# Audio.net
KiCad netlist of a schematic drawn in Altium Designer
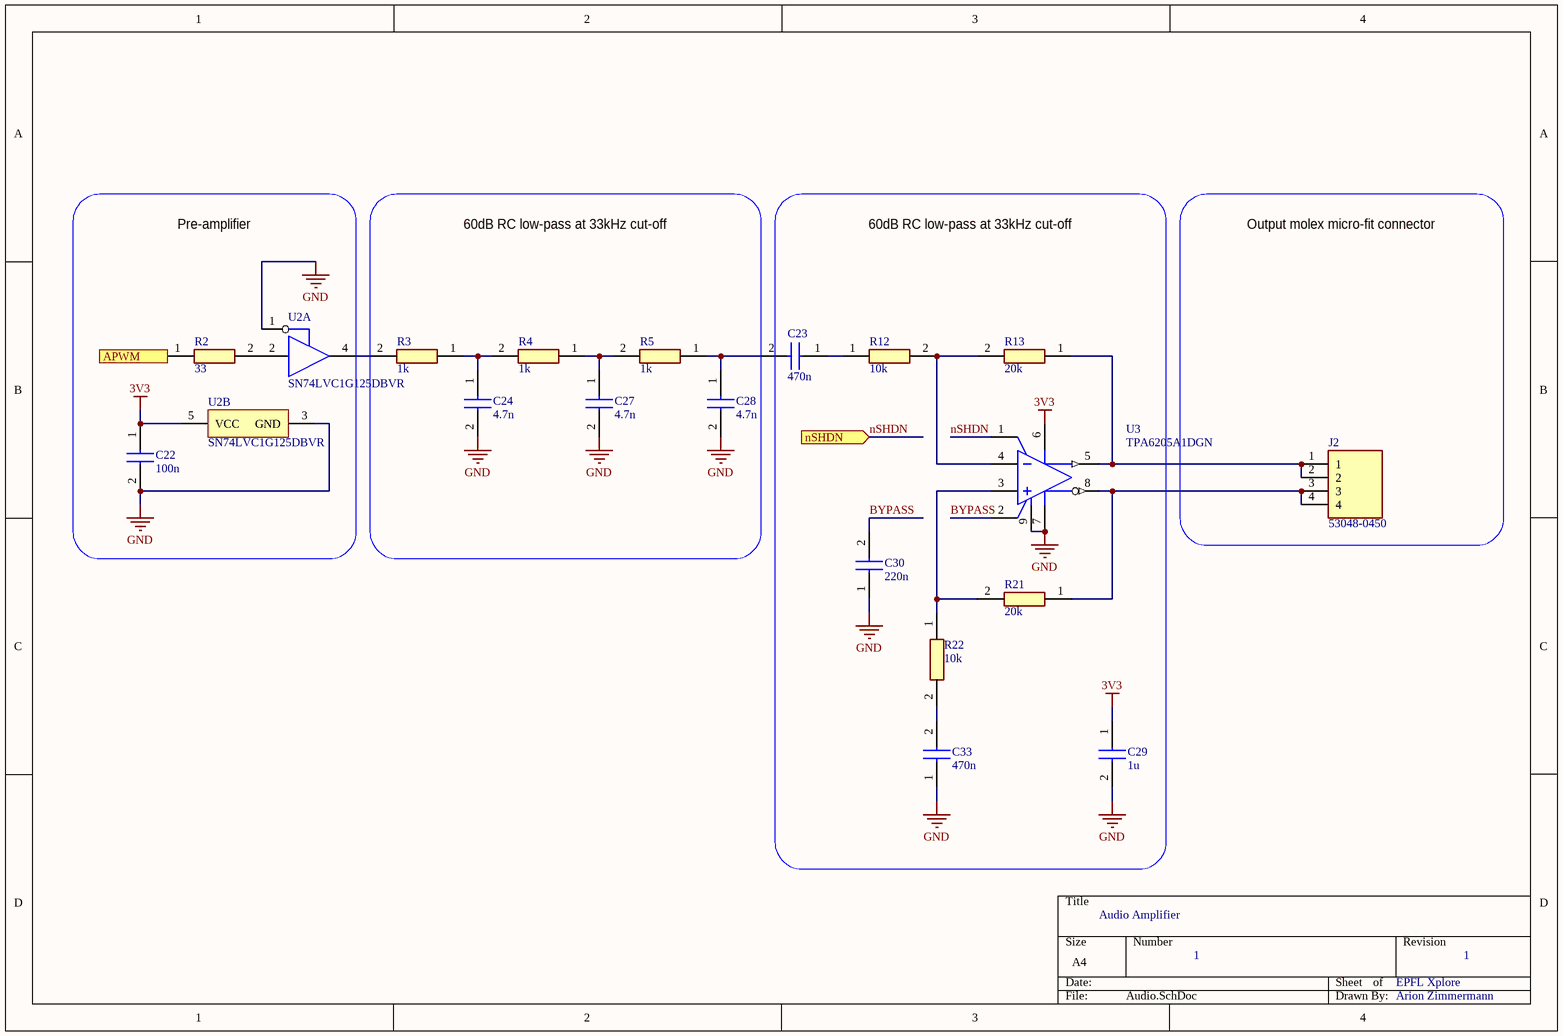
[diagram p0: Audio.SchDoc]

(export (version "E")
  (design (tool "Eeschema 10.0.6"))
  (components
    (comp (ref "C22")
      (value "100n")
      (footprint "SamacSys:CAPC1608X95N")
      (description "Capacitor")
      (fields
        (field (name "MANUFACTURER_PART_NUMBER") "C0603C104K5RACTU")
        (field (name "MOUSER PART NUMBER") "80-C0603C104K5R")
      )
      (libsource (lib "CarrierBoard") (part "C0603C104K5RACTU"))
    )
    (comp (ref "C23")
      (value "470n")
      (footprint "SamacSys:CAPC1608X95N")
      (description "Capacitor")
      (fields
        (field (name "MANUFACTURER_PART_NUMBER") "C0603C104K5RACTU")
        (field (name "MOUSER PART NUMBER") "80-C0603C104K5R")
      )
      (libsource (lib "CarrierBoard") (part "C0603C104K5RACTU"))
    )
    (comp (ref "C24")
      (value "4.7n")
      (footprint "SamacSys:CAPC1608X95N")
      (description "Capacitor")
      (fields
        (field (name "MANUFACTURER_PART_NUMBER") "C0603C104K5RACTU")
        (field (name "MOUSER PART NUMBER") "80-C0603C104K5R")
      )
      (libsource (lib "CarrierBoard") (part "C0603C104K5RACTU"))
    )
    (comp (ref "C27")
      (value "4.7n")
      (footprint "SamacSys:CAPC1608X95N")
      (description "Capacitor")
      (fields
        (field (name "MANUFACTURER_PART_NUMBER") "C0603C104K5RACTU")
        (field (name "MOUSER PART NUMBER") "80-C0603C104K5R")
      )
      (libsource (lib "CarrierBoard") (part "C0603C104K5RACTU"))
    )
    (comp (ref "C28")
      (value "4.7n")
      (footprint "SamacSys:CAPC1608X95N")
      (description "Capacitor")
      (fields
        (field (name "MANUFACTURER_PART_NUMBER") "C0603C104K5RACTU")
        (field (name "MOUSER PART NUMBER") "80-C0603C104K5R")
      )
      (libsource (lib "CarrierBoard") (part "C0603C104K5RACTU"))
    )
    (comp (ref "C29")
      (value "1u")
      (footprint "SamacSys:CAPC1608X95N")
      (description "Capacitor")
      (fields
        (field (name "MANUFACTURER_PART_NUMBER") "C0603C104K5RACTU")
        (field (name "MOUSER PART NUMBER") "80-C0603C104K5R")
      )
      (libsource (lib "CarrierBoard") (part "C0603C104K5RACTU"))
    )
    (comp (ref "C30")
      (value "220n")
      (footprint "SamacSys:CAPC1608X95N")
      (description "Capacitor")
      (fields
        (field (name "MANUFACTURER_PART_NUMBER") "C0603C104K5RACTU")
        (field (name "MOUSER PART NUMBER") "80-C0603C104K5R")
      )
      (libsource (lib "CarrierBoard") (part "C0603C104K5RACTU"))
    )
    (comp (ref "C33")
      (value "470n")
      (footprint "SamacSys:CAPC1608X95N")
      (description "Capacitor")
      (fields
        (field (name "MANUFACTURER_PART_NUMBER") "C0603C104K5RACTU")
        (field (name "MOUSER PART NUMBER") "80-C0603C104K5R")
      )
      (libsource (lib "CarrierBoard") (part "C0603C104K5RACTU"))
    )
    (comp (ref "J2")
      (value "53048-0450")
      (footprint "SHDRRA4W35P0X125_1X4_675X550X350P")
      (description "Connector")
      (fields (field (name "MOUSER PART NUMBER") "538-53048-0450"))
      (libsource (lib "*") (part "53048-0450"))
    )
    (comp (ref "R2")
      (value "33")
      (footprint "SamacSys:RESC1608X50N")
      (description "Resistor")
      (fields
        (field (name "MANUFACTURER_PART_NUMBER") "CRCW0603787RFKEA")
        (field (name "Comment") "CRCW060333R0JNEAC")
      )
      (libsource (lib "CarrierBoard") (part "CRCW0603931RFKEA"))
    )
    (comp (ref "R3")
      (value "1k")
      (footprint "SamacSys:RESC1608X50N")
      (description "Resistor")
      (fields
        (field (name "MANUFACTURER_PART_NUMBER") "CRCW0603787RFKEA")
        (field (name "Comment") "CRCW06031K00FKECC")
      )
      (libsource (lib "") (part "CRCW0603931RFKEA_1"))
    )
    (comp (ref "R4")
      (value "1k")
      (footprint "SamacSys:RESC1608X50N")
      (description "Resistor")
      (fields
        (field (name "MANUFACTURER_PART_NUMBER") "CRCW0603787RFKEA")
        (field (name "Comment") "CRCW06031K00FKECC")
      )
      (libsource (lib "") (part "CRCW0603931RFKEA_1"))
    )
    (comp (ref "R5")
      (value "1k")
      (footprint "SamacSys:RESC1608X50N")
      (description "Resistor")
      (fields
        (field (name "MANUFACTURER_PART_NUMBER") "CRCW0603787RFKEA")
        (field (name "Comment") "CRCW06031K00FKECC")
      )
      (libsource (lib "") (part "CRCW0603931RFKEA_1"))
    )
    (comp (ref "R12")
      (value "10k")
      (footprint "SamacSys:RESC1608X50N")
      (description "Resistor")
      (fields
        (field (name "MANUFACTURER_PART_NUMBER") "CRCW0603787RFKEA")
        (field (name "Comment") "CRCW060310K2FKEA")
      )
      (libsource (lib "CarrierBoard") (part "CRCW0603931RFKEA"))
    )
    (comp (ref "R13")
      (value "20k")
      (footprint "SamacSys:RESC1608X50N")
      (description "Resistor")
      (fields
        (field (name "MANUFACTURER_PART_NUMBER") "CRCW0603787RFKEA")
        (field (name "Comment") "CRCW060320K0FKEAC")
      )
      (libsource (lib "") (part "CRCW0603931RFKEA_1"))
    )
    (comp (ref "R21")
      (value "20k")
      (footprint "SamacSys:RESC1608X50N")
      (description "Resistor")
      (fields
        (field (name "MANUFACTURER_PART_NUMBER") "CRCW0603787RFKEA")
        (field (name "Comment") "CRCW060320K0FKEAC")
      )
      (libsource (lib "") (part "CRCW0603931RFKEA_1"))
    )
    (comp (ref "R22")
      (value "10k")
      (footprint "SamacSys:RESC1608X50N")
      (description "Resistor")
      (fields
        (field (name "MANUFACTURER_PART_NUMBER") "CRCW0603787RFKEA")
        (field (name "Comment") "CRCW060310K2FKEA")
      )
      (libsource (lib "") (part "CRCW0603931RFKEA_2"))
    )
    (comp (ref "U2")
      (value "SN74LVC1G125DBVR")
      (footprint "DBV0005A_M")
      (description "Single Bus Buffer Gate With 3-State Outputs, DBV0005A, LARGE T&R")
      (fields
        (field (name "GENERIC PART NUMBER") "SN74LVC1G125")
        (field (name "MANUFACTURER") "Texas Instruments")
      )
      (libsource (lib "") (part "TI-SN74AXXXX1X125-5_1"))
    )
    (comp (ref "U3")
      (value "TPA6205A1DGN")
      (footprint "DGN0008D_N")
      (fields (field (name "MANUFACTURER") "Texas Instruments"))
      (libsource (lib "Altium Content Vault") (part "TI-TPA62XXA1DXX8-TP"))
    )
  )
  (nets
    (net (code "1") (name "/APWM") (class "Default")
      (node (ref "R2") (pin "1") (pinfunction "1_1") (pintype "passive"))
    )
    (net (code "2") (name "/BYPASS") (class "Default")
      (node (ref "C30") (pin "2") (pinfunction "2_2") (pintype "passive"))
      (node (ref "U3") (pin "2") (pinfunction "BYPASS_2") (pintype "passive"))
    )
    (net (code "3") (name "/nSHDN") (class "Default")
      (node (ref "U3") (pin "1") (pinfunction "~{SHUTDOWN}_1") (pintype "passive"))
    )
    (net (code "4") (name "3V3") (class "Default")
      (node (ref "C22") (pin "1") (pinfunction "1_1") (pintype "passive"))
      (node (ref "C29") (pin "1") (pinfunction "1_1") (pintype "passive"))
      (node (ref "U2") (pin "5") (pinfunction "VCC_5") (pintype "power_in"))
      (node (ref "U3") (pin "6") (pinfunction "VDD_6") (pintype "power_in"))
    )
    (net (code "5") (name "GND") (class "Default")
      (node (ref "C22") (pin "2") (pinfunction "2_2") (pintype "passive"))
      (node (ref "C24") (pin "2") (pinfunction "2_2") (pintype "passive"))
      (node (ref "C27") (pin "2") (pinfunction "2_2") (pintype "passive"))
      (node (ref "C28") (pin "2") (pinfunction "2_2") (pintype "passive"))
      (node (ref "C29") (pin "2") (pinfunction "2_2") (pintype "passive"))
      (node (ref "C30") (pin "1") (pinfunction "1_1") (pintype "passive"))
      (node (ref "C33") (pin "1") (pinfunction "1_1") (pintype "passive"))
      (node (ref "U2") (pin "1") (pinfunction "~{OE}_1") (pintype "passive"))
      (node (ref "U2") (pin "3") (pinfunction "GND_3") (pintype "power_in"))
      (node (ref "U3") (pin "7") (pinfunction "GND_7") (pintype "power_in"))
      (node (ref "U3") (pin "9") (pinfunction "EP_9") (pintype "power_in"))
    )
    (net (code "6") (name "Net-(C23-Pad1)") (class "Default")
      (node (ref "C23") (pin "1") (pinfunction "1_1") (pintype "passive"))
      (node (ref "R12") (pin "1") (pinfunction "1_1") (pintype "passive"))
    )
    (net (code "7") (name "Net-(C23-Pad2)") (class "Default")
      (node (ref "C23") (pin "2") (pinfunction "2_2") (pintype "passive"))
      (node (ref "C28") (pin "1") (pinfunction "1_1") (pintype "passive"))
      (node (ref "R5") (pin "1") (pinfunction "1_1") (pintype "passive"))
    )
    (net (code "8") (name "Net-(C24-Pad1)") (class "Default")
      (node (ref "C24") (pin "1") (pinfunction "1_1") (pintype "passive"))
      (node (ref "R3") (pin "1") (pinfunction "1_1") (pintype "passive"))
      (node (ref "R4") (pin "2") (pinfunction "2_2") (pintype "passive"))
    )
    (net (code "9") (name "Net-(C27-Pad1)") (class "Default")
      (node (ref "C27") (pin "1") (pinfunction "1_1") (pintype "passive"))
      (node (ref "R4") (pin "1") (pinfunction "1_1") (pintype "passive"))
      (node (ref "R5") (pin "2") (pinfunction "2_2") (pintype "passive"))
    )
    (net (code "10") (name "Net-(C33-Pad2)") (class "Default")
      (node (ref "C33") (pin "2") (pinfunction "2_2") (pintype "passive"))
      (node (ref "R22") (pin "2") (pinfunction "2_2") (pintype "passive"))
    )
    (net (code "11") (name "Net-(U2A-A)") (class "Default")
      (node (ref "R2") (pin "2") (pinfunction "2_2") (pintype "passive"))
      (node (ref "U2") (pin "2") (pinfunction "A_2") (pintype "passive"))
    )
    (net (code "12") (name "Net-(U2A-Y)") (class "Default")
      (node (ref "R3") (pin "2") (pinfunction "2_2") (pintype "passive"))
      (node (ref "U2") (pin "4") (pinfunction "Y_4") (pintype "tri_state"))
    )
    (net (code "13") (name "Net-(U3-IN+)") (class "Default")
      (node (ref "R21") (pin "2") (pinfunction "2_2") (pintype "passive"))
      (node (ref "R22") (pin "1") (pinfunction "1_1") (pintype "passive"))
      (node (ref "U3") (pin "3") (pinfunction "IN+_3") (pintype "passive"))
    )
    (net (code "14") (name "Net-(U3-IN-)") (class "Default")
      (node (ref "R12") (pin "2") (pinfunction "2_2") (pintype "passive"))
      (node (ref "R13") (pin "2") (pinfunction "2_2") (pintype "passive"))
      (node (ref "U3") (pin "4") (pinfunction "IN-_4") (pintype "passive"))
    )
    (net (code "15") (name "Net-(U3-VO+)") (class "Default")
      (node (ref "J2") (pin "1") (pinfunction "1_1") (pintype "passive"))
      (node (ref "J2") (pin "2") (pinfunction "2_2") (pintype "passive"))
      (node (ref "R13") (pin "1") (pinfunction "1_1") (pintype "passive"))
      (node (ref "U3") (pin "5") (pinfunction "VO+_5") (pintype "output"))
    )
    (net (code "16") (name "Net-(U3-VO-)") (class "Default")
      (node (ref "J2") (pin "3") (pinfunction "3_3") (pintype "passive"))
      (node (ref "J2") (pin "4") (pinfunction "4_4") (pintype "passive"))
      (node (ref "R21") (pin "1") (pinfunction "1_1") (pintype "passive"))
      (node (ref "U3") (pin "8") (pinfunction "VO-_8") (pintype "output"))
    )
  )
)
